# BMW_E34_Start-Stop_Btn_v2.net
KiCad netlist of a schematic drawn in Altium Designer
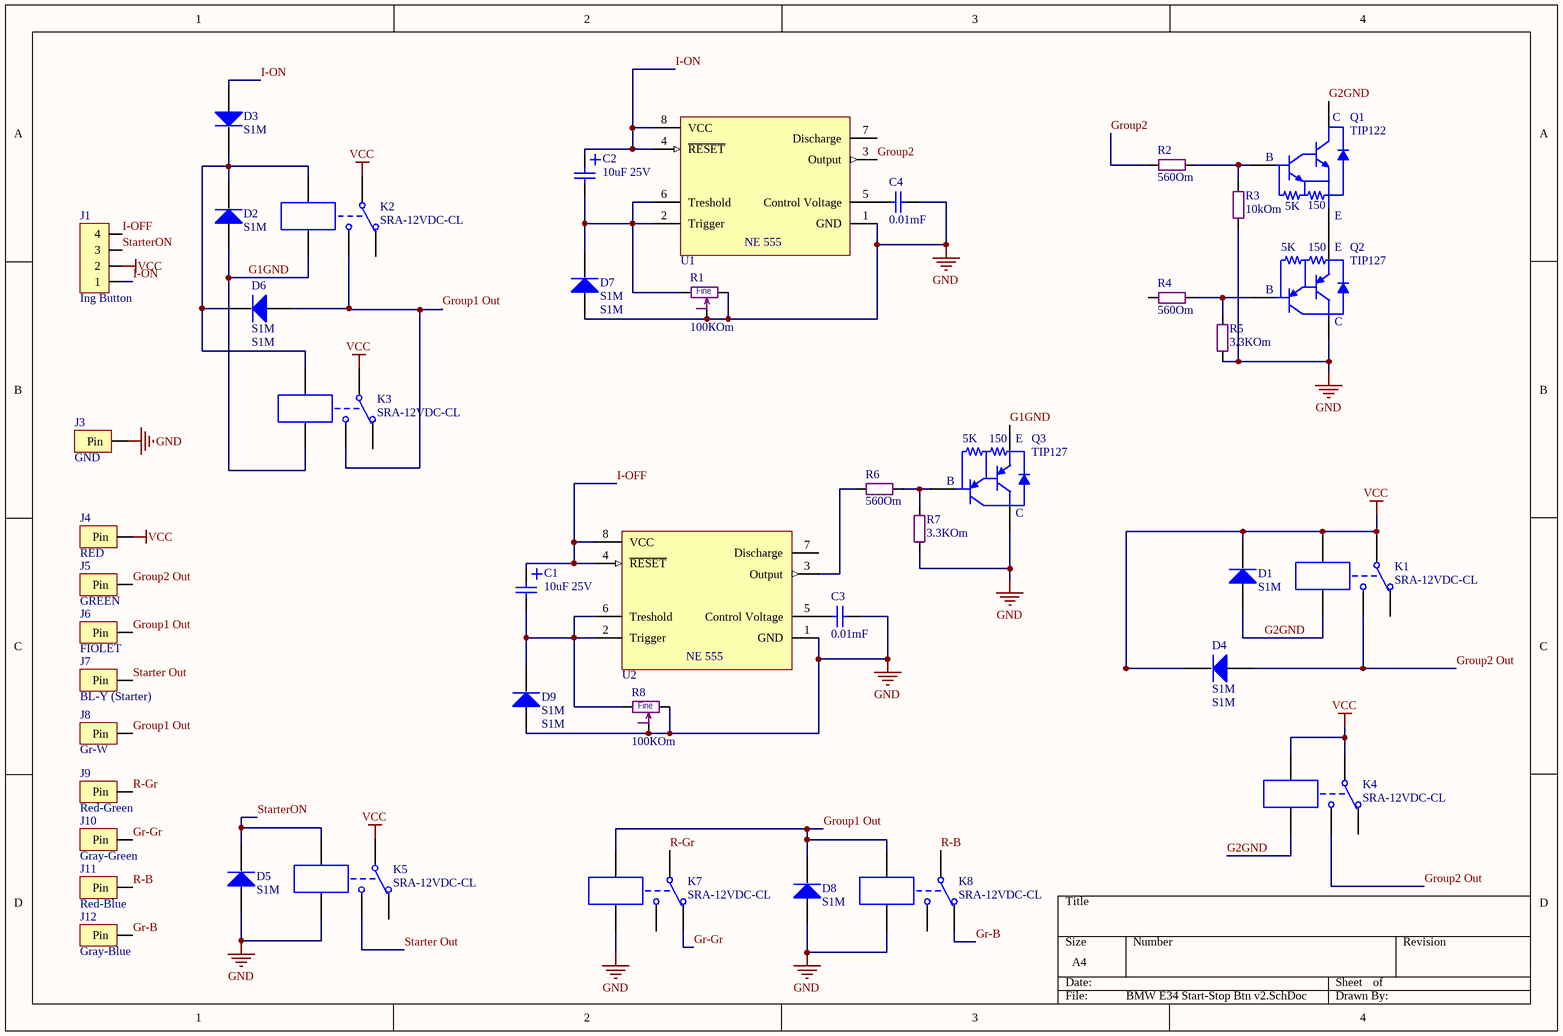
[diagram p0: BMW E34 Start-Stop Btn v2.SchDoc]

(export (version "E")
  (design (tool "Eeschema 10.0.6"))
  (components
    (comp (ref "C1")
      (value "10uF 25V")
      (footprint "Capacitor:Cap E p2mm D6.5xH11")
      (description "Capacitor")
      (libsource (lib "Capacitor") (part "Cap E 220mF x 16V"))
    )
    (comp (ref "C2")
      (value "10uF 25V")
      (footprint "Capacitor:Cap E p2mm D6.5xH11")
      (description "Capacitor")
      (libsource (lib "Capacitor") (part "Cap E 220mF x 16V"))
    )
    (comp (ref "C3")
      (value "0.01mF")
      (footprint "Capacitor:Cap p2.54mm (2p)")
      (description "Capacitor")
      (libsource (lib "Capacitor") (part "Cap Ceramic"))
    )
    (comp (ref "C4")
      (value "0.01mF")
      (footprint "Capacitor:Cap p2.54mm (2p)")
      (description "Capacitor")
      (libsource (lib "Capacitor") (part "Cap Ceramic"))
    )
    (comp (ref "D1")
      (value "S1M")
      (footprint "Diodes:DO-214AC")
      (description "1 Amp General Purpose Rectifier")
      (libsource (lib "Diodes") (part "Diode S1M"))
    )
    (comp (ref "D2")
      (value "S1M")
      (footprint "Diodes:DO-214AC")
      (description "1 Amp General Purpose Rectifier")
      (libsource (lib "Diodes") (part "Diode S1M"))
    )
    (comp (ref "D3")
      (value "S1M")
      (footprint "Diodes:DO-214AC")
      (description "1 Amp General Purpose Rectifier")
      (libsource (lib "Diodes") (part "Diode S1M"))
    )
    (comp (ref "D4")
      (value "S1M")
      (footprint "Diodes:DO-214AC")
      (description "1 Amp General Purpose Rectifier")
      (fields (field (name "ALTIUM_VALUE") "S1M"))
      (libsource (lib "Diodes") (part "Diode S1M"))
    )
    (comp (ref "D5")
      (value "S1M")
      (footprint "Diodes:DO-214AC")
      (description "1 Amp General Purpose Rectifier")
      (libsource (lib "Diodes") (part "Diode S1M"))
    )
    (comp (ref "D6")
      (value "S1M")
      (footprint "Diodes:DO-214AC")
      (description "1 Amp General Purpose Rectifier")
      (fields (field (name "ALTIUM_VALUE") "S1M"))
      (libsource (lib "Diodes") (part "Diode S1M"))
    )
    (comp (ref "D7")
      (value "S1M")
      (footprint "Diodes:DO-214AC")
      (description "1 Amp General Purpose Rectifier")
      (fields (field (name "ALTIUM_VALUE") "S1M"))
      (libsource (lib "Diodes") (part "Diode S1M"))
    )
    (comp (ref "D8")
      (value "S1M")
      (footprint "Diodes:DO-214AC")
      (description "1 Amp General Purpose Rectifier")
      (libsource (lib "Diodes") (part "Diode S1M"))
    )
    (comp (ref "D9")
      (value "S1M")
      (footprint "Diodes:DO-214AC")
      (description "1 Amp General Purpose Rectifier")
      (fields (field (name "ALTIUM_VALUE") "S1M"))
      (libsource (lib "Diodes") (part "Diode S1M"))
    )
    (comp (ref "J1")
      (value "Ing Button")
      (footprint "Connector:Molex Micro-Fit 3.0 - 4 pin D R")
      (description "Horisontal, Dbl line, Male - 3mm")
      (fields (field (name "PART NUMBER") "0430450402"))
      (libsource (lib "Connector") (part "Micro-Fit 4R (2x2)"))
    )
    (comp (ref "J3")
      (value "GND")
      (footprint "Connector:OnePin 1.2x3")
      (description "Only pad")
      (libsource (lib "Connector") (part "OnePin Connector"))
    )
    (comp (ref "J4")
      (value "RED")
      (footprint "Connector:OnePin 1.5x4")
      (description "Only pad")
      (libsource (lib "Connector") (part "OnePin Connector"))
    )
    (comp (ref "J5")
      (value "GREEN")
      (footprint "Connector:OnePin 1.5x4")
      (description "Only pad")
      (libsource (lib "Connector") (part "OnePin Connector"))
    )
    (comp (ref "J6")
      (value "FIOLET")
      (footprint "Connector:OnePin 1.5x4")
      (description "Only pad")
      (libsource (lib "Connector") (part "OnePin Connector"))
    )
    (comp (ref "J7")
      (value "BL-Y (Starter)")
      (footprint "Connector:OnePin 1.5x4")
      (description "Only pad")
      (libsource (lib "Connector") (part "OnePin Connector"))
    )
    (comp (ref "J8")
      (value "Gr-W")
      (footprint "Connector:OnePin 1x2.5")
      (description "Only pad")
      (libsource (lib "Connector") (part "OnePin Connector"))
    )
    (comp (ref "J9")
      (value "Red-Green")
      (footprint "Connector:OnePin 1x2.5")
      (description "Only pad")
      (libsource (lib "Connector") (part "OnePin Connector"))
    )
    (comp (ref "J10")
      (value "Gray-Green")
      (footprint "Connector:OnePin 1x2.5")
      (description "Only pad")
      (libsource (lib "Connector") (part "OnePin Connector"))
    )
    (comp (ref "J11")
      (value "Red-Blue")
      (footprint "Connector:OnePin 1x2.5")
      (description "Only pad")
      (libsource (lib "Connector") (part "OnePin Connector"))
    )
    (comp (ref "J12")
      (value "Gray-Blue")
      (footprint "Connector:OnePin 1x2.5")
      (description "Only pad")
      (libsource (lib "Connector") (part "OnePin Connector"))
    )
    (comp (ref "K1")
      (value "SRA-12VDC-CL")
      (footprint "Relay:SRA-12VDC-CL")
      (description "Single-Pole Dual-Throw Relay")
      (libsource (lib "Relay") (part "SRA-12VDC-CL"))
    )
    (comp (ref "K2")
      (value "SRA-12VDC-CL")
      (footprint "Relay:SRA-12VDC-CL")
      (description "Single-Pole Dual-Throw Relay")
      (libsource (lib "Relay") (part "SRA-12VDC-CL"))
    )
    (comp (ref "K3")
      (value "SRA-12VDC-CL")
      (footprint "Relay:SRA-12VDC-CL")
      (description "Single-Pole Dual-Throw Relay")
      (libsource (lib "Relay") (part "SRA-12VDC-CL"))
    )
    (comp (ref "K4")
      (value "SRA-12VDC-CL")
      (footprint "Relay:SRA-12VDC-CL")
      (description "Single-Pole Dual-Throw Relay")
      (libsource (lib "Relay") (part "SRA-12VDC-CL"))
    )
    (comp (ref "K5")
      (value "SRA-12VDC-CL")
      (footprint "Relay:SRA-12VDC-CL")
      (description "Single-Pole Dual-Throw Relay")
      (libsource (lib "Relay") (part "SRA-12VDC-CL"))
    )
    (comp (ref "K7")
      (value "SRA-12VDC-CL")
      (footprint "Relay:SRA-12VDC-CL")
      (description "Single-Pole Dual-Throw Relay")
      (libsource (lib "Relay") (part "SRA-12VDC-CL"))
    )
    (comp (ref "K8")
      (value "SRA-12VDC-CL")
      (footprint "Relay:SRA-12VDC-CL")
      (description "Single-Pole Dual-Throw Relay")
      (libsource (lib "Relay") (part "SRA-12VDC-CL"))
    )
    (comp (ref "Q1")
      (value "TIP122")
      (footprint "GeneralCases:TO220-2")
      (description "NPN Darlington 5A, 65W, 100V, h>1000")
      (libsource (lib "Transistor") (part "TIP122"))
    )
    (comp (ref "Q2")
      (value "TIP127")
      (footprint "GeneralCases:TO220-2")
      (description "PNP Darlington Bipolar Transistor")
      (libsource (lib "Transistor") (part "TIP127"))
    )
    (comp (ref "Q3")
      (value "TIP127")
      (footprint "GeneralCases:TO220-2")
      (description "PNP Darlington Bipolar Transistor")
      (libsource (lib "Transistor") (part "TIP127"))
    )
    (comp (ref "R1")
      (value "100КOm")
      (footprint "PassiveComponents:Res Adj 3362P")
      (libsource (lib "PassiveComponents") (part "Res Adj 3362"))
    )
    (comp (ref "R2")
      (value "560Om")
      (footprint "PassiveComponents:SMD 0805 (2012)")
      (libsource (lib "PassiveComponents") (part "Res All Types"))
    )
    (comp (ref "R3")
      (value "10kOm")
      (footprint "PassiveComponents:SMD 0805 (2012)")
      (libsource (lib "PassiveComponents") (part "Res All Types"))
    )
    (comp (ref "R4")
      (value "560Om")
      (footprint "PassiveComponents:SMD 0805 (2012)")
      (libsource (lib "PassiveComponents") (part "Res All Types"))
    )
    (comp (ref "R5")
      (value "3.3KOm")
      (footprint "PassiveComponents:SMD 0805 (2012)")
      (libsource (lib "PassiveComponents") (part "Res All Types"))
    )
    (comp (ref "R6")
      (value "560Om")
      (footprint "PassiveComponents:SMD 0805 (2012)")
      (libsource (lib "PassiveComponents") (part "Res All Types"))
    )
    (comp (ref "R7")
      (value "3.3KOm")
      (footprint "PassiveComponents:SMD 0805 (2012)")
      (libsource (lib "PassiveComponents") (part "Res All Types"))
    )
    (comp (ref "R8")
      (value "100КOm")
      (footprint "PassiveComponents:Res Adj 3362P")
      (libsource (lib "PassiveComponents") (part "Res Adj 3362"))
    )
    (comp (ref "U1")
      (value "NE555")
      (footprint "GeneralCases:DIP-8")
      (description "8-Bit Shift Register with 3-State Output Registers")
      (libsource (lib "Chips") (part "NE555"))
    )
    (comp (ref "U2")
      (value "NE555")
      (footprint "GeneralCases:DIP-8")
      (description "8-Bit Shift Register with 3-State Output Registers")
      (libsource (lib "Chips") (part "NE555"))
    )
  )
  (nets
    (net (code "1") (name "/G1GND") (class "Default")
      (node (ref "D2") (pin "A") (pinfunction "A_A") (pintype "passive"))
      (node (ref "K2") (pin "5") (pinfunction "5_5") (pintype "passive"))
      (node (ref "K3") (pin "5") (pinfunction "5_5") (pintype "passive"))
      (node (ref "Q3") (pin "3") (pinfunction "E_3") (pintype "passive"))
    )
    (net (code "2") (name "/G2GND") (class "Default")
      (node (ref "D1") (pin "A") (pinfunction "A_A") (pintype "passive"))
      (node (ref "K1") (pin "5") (pinfunction "5_5") (pintype "passive"))
      (node (ref "K4") (pin "5") (pinfunction "5_5") (pintype "passive"))
      (node (ref "Q1") (pin "2") (pinfunction "C_2") (pintype "passive"))
    )
    (net (code "3") (name "/Gr-B") (class "Default")
      (node (ref "J12") (pin "1") (pinfunction "Pin_1") (pintype "passive"))
      (node (ref "K8") (pin "1") (pinfunction "1_1") (pintype "passive"))
    )
    (net (code "4") (name "/Gr-Gr") (class "Default")
      (node (ref "J10") (pin "1") (pinfunction "Pin_1") (pintype "passive"))
      (node (ref "K7") (pin "1") (pinfunction "1_1") (pintype "passive"))
    )
    (net (code "5") (name "/Group1 Out") (class "Default")
      (node (ref "D6") (pin "A") (pinfunction "A_A") (pintype "passive"))
      (node (ref "D8") (pin "K") (pinfunction "K_K") (pintype "passive"))
      (node (ref "J6") (pin "1") (pinfunction "Pin_1") (pintype "passive"))
      (node (ref "J8") (pin "1") (pinfunction "Pin_1") (pintype "passive"))
      (node (ref "K2") (pin "3") (pinfunction "3_3") (pintype "passive"))
      (node (ref "K3") (pin "3") (pinfunction "3_3") (pintype "passive"))
      (node (ref "K7") (pin "4") (pinfunction "4_4") (pintype "passive"))
      (node (ref "K8") (pin "4") (pinfunction "4_4") (pintype "passive"))
    )
    (net (code "6") (name "/Group2") (class "Default")
      (node (ref "R2") (pin "1") (pinfunction "1_1") (pintype "passive"))
      (node (ref "U1") (pin "3") (pinfunction "Output_3") (pintype "output"))
    )
    (net (code "7") (name "/Group2 Out") (class "Default")
      (node (ref "D4") (pin "A") (pinfunction "A_A") (pintype "passive"))
      (node (ref "J5") (pin "1") (pinfunction "Pin_1") (pintype "passive"))
      (node (ref "K1") (pin "3") (pinfunction "3_3") (pintype "passive"))
      (node (ref "K4") (pin "3") (pinfunction "3_3") (pintype "passive"))
    )
    (net (code "8") (name "/I-OFF") (class "Default")
      (node (ref "C1") (pin "1") (pinfunction "1_1") (pintype "passive"))
      (node (ref "J1") (pin "4") (pinfunction "4_4") (pintype "passive"))
      (node (ref "U2") (pin "4") (pinfunction "~{RESET}_4") (pintype "input"))
      (node (ref "U2") (pin "8") (pinfunction "VCC_8") (pintype "power_in"))
    )
    (net (code "9") (name "/I-ON") (class "Default")
      (node (ref "C2") (pin "1") (pinfunction "1_1") (pintype "passive"))
      (node (ref "D3") (pin "A") (pinfunction "A_A") (pintype "passive"))
      (node (ref "J1") (pin "1") (pinfunction "1_1") (pintype "passive"))
      (node (ref "U1") (pin "4") (pinfunction "~{RESET}_4") (pintype "input"))
      (node (ref "U1") (pin "8") (pinfunction "VCC_8") (pintype "power_in"))
    )
    (net (code "10") (name "/R-B") (class "Default")
      (node (ref "J11") (pin "1") (pinfunction "Pin_1") (pintype "passive"))
      (node (ref "K8") (pin "2") (pinfunction "2_2") (pintype "passive"))
    )
    (net (code "11") (name "/R-Gr") (class "Default")
      (node (ref "J9") (pin "1") (pinfunction "Pin_1") (pintype "passive"))
      (node (ref "K7") (pin "2") (pinfunction "2_2") (pintype "passive"))
    )
    (net (code "12") (name "/Starter Out") (class "Default")
      (node (ref "J7") (pin "1") (pinfunction "Pin_1") (pintype "passive"))
      (node (ref "K5") (pin "3") (pinfunction "3_3") (pintype "passive"))
    )
    (net (code "13") (name "/StarterON") (class "Default")
      (node (ref "D5") (pin "K") (pinfunction "K_K") (pintype "passive"))
      (node (ref "J1") (pin "3") (pinfunction "3_3") (pintype "passive"))
      (node (ref "K5") (pin "4") (pinfunction "4_4") (pintype "passive"))
    )
    (net (code "14") (name "GND") (class "Default")
      (node (ref "C3") (pin "2") (pinfunction "2_2") (pintype "passive"))
      (node (ref "C4") (pin "2") (pinfunction "2_2") (pintype "passive"))
      (node (ref "D5") (pin "A") (pinfunction "A_A") (pintype "passive"))
      (node (ref "D7") (pin "A") (pinfunction "A_A") (pintype "passive"))
      (node (ref "D8") (pin "A") (pinfunction "A_A") (pintype "passive"))
      (node (ref "D9") (pin "A") (pinfunction "A_A") (pintype "passive"))
      (node (ref "J3") (pin "1") (pinfunction "Pin_1") (pintype "passive"))
      (node (ref "K5") (pin "5") (pinfunction "5_5") (pintype "passive"))
      (node (ref "K7") (pin "5") (pinfunction "5_5") (pintype "passive"))
      (node (ref "K8") (pin "5") (pinfunction "5_5") (pintype "passive"))
      (node (ref "Q2") (pin "2") (pinfunction "C_2") (pintype "passive"))
      (node (ref "Q3") (pin "2") (pinfunction "C_2") (pintype "passive"))
      (node (ref "R1") (pin "2") (pinfunction "2_2") (pintype "passive"))
      (node (ref "R1") (pin "3") (pinfunction "3_3") (pintype "passive"))
      (node (ref "R3") (pin "1") (pinfunction "1_1") (pintype "passive"))
      (node (ref "R5") (pin "1") (pinfunction "1_1") (pintype "passive"))
      (node (ref "R7") (pin "1") (pinfunction "1_1") (pintype "passive"))
      (node (ref "R8") (pin "2") (pinfunction "2_2") (pintype "passive"))
      (node (ref "R8") (pin "3") (pinfunction "3_3") (pintype "passive"))
      (node (ref "U1") (pin "1") (pinfunction "GND_1") (pintype "power_in"))
      (node (ref "U2") (pin "1") (pinfunction "GND_1") (pintype "power_in"))
    )
    (net (code "15") (name "Net-(D2-PadK)") (class "Default")
      (node (ref "D2") (pin "K") (pinfunction "K_K") (pintype "passive"))
      (node (ref "D3") (pin "K") (pinfunction "K_K") (pintype "passive"))
      (node (ref "D6") (pin "K") (pinfunction "K_K") (pintype "passive"))
      (node (ref "K2") (pin "4") (pinfunction "4_4") (pintype "passive"))
      (node (ref "K3") (pin "4") (pinfunction "4_4") (pintype "passive"))
    )
    (net (code "16") (name "Net-(Q1-B)") (class "Default")
      (node (ref "Q1") (pin "1") (pinfunction "B_1") (pintype "passive"))
      (node (ref "R2") (pin "2") (pinfunction "2_2") (pintype "passive"))
      (node (ref "R3") (pin "2") (pinfunction "2_2") (pintype "passive"))
    )
    (net (code "17") (name "Net-(Q1-E)") (class "Default")
      (node (ref "Q1") (pin "3") (pinfunction "E_3") (pintype "passive"))
      (node (ref "Q2") (pin "3") (pinfunction "E_3") (pintype "passive"))
    )
    (net (code "18") (name "Net-(Q2-B)") (class "Default")
      (node (ref "Q2") (pin "1") (pinfunction "B_1") (pintype "passive"))
      (node (ref "R4") (pin "2") (pinfunction "2_2") (pintype "passive"))
      (node (ref "R5") (pin "2") (pinfunction "2_2") (pintype "passive"))
    )
    (net (code "19") (name "Net-(Q3-B)") (class "Default")
      (node (ref "Q3") (pin "1") (pinfunction "B_1") (pintype "passive"))
      (node (ref "R6") (pin "2") (pinfunction "2_2") (pintype "passive"))
      (node (ref "R7") (pin "2") (pinfunction "2_2") (pintype "passive"))
    )
    (net (code "20") (name "Net-(U1-Control_Voltage)") (class "Default")
      (node (ref "C4") (pin "1") (pinfunction "1_1") (pintype "passive"))
      (node (ref "U1") (pin "5") (pinfunction "Control_Voltage_5") (pintype "tri_state"))
    )
    (net (code "21") (name "Net-(U1-Treshold)") (class "Default")
      (node (ref "C2") (pin "2") (pinfunction "2_2") (pintype "passive"))
      (node (ref "D7") (pin "K") (pinfunction "K_K") (pintype "passive"))
      (node (ref "R1") (pin "1") (pinfunction "1_1") (pintype "passive"))
      (node (ref "U1") (pin "2") (pinfunction "Trigger_2") (pintype "tri_state"))
      (node (ref "U1") (pin "6") (pinfunction "Treshold_6") (pintype "tri_state"))
    )
    (net (code "22") (name "Net-(U2-Control_Voltage)") (class "Default")
      (node (ref "C3") (pin "1") (pinfunction "1_1") (pintype "passive"))
      (node (ref "U2") (pin "5") (pinfunction "Control_Voltage_5") (pintype "tri_state"))
    )
    (net (code "23") (name "Net-(U2-Output)") (class "Default")
      (node (ref "R6") (pin "1") (pinfunction "1_1") (pintype "passive"))
      (node (ref "U2") (pin "3") (pinfunction "Output_3") (pintype "output"))
    )
    (net (code "24") (name "Net-(U2-Treshold)") (class "Default")
      (node (ref "C1") (pin "2") (pinfunction "2_2") (pintype "passive"))
      (node (ref "D9") (pin "K") (pinfunction "K_K") (pintype "passive"))
      (node (ref "R8") (pin "1") (pinfunction "1_1") (pintype "passive"))
      (node (ref "U2") (pin "2") (pinfunction "Trigger_2") (pintype "tri_state"))
      (node (ref "U2") (pin "6") (pinfunction "Treshold_6") (pintype "tri_state"))
    )
    (net (code "25") (name "VCC") (class "Default")
      (node (ref "D1") (pin "K") (pinfunction "K_K") (pintype "passive"))
      (node (ref "D4") (pin "K") (pinfunction "K_K") (pintype "passive"))
      (node (ref "J1") (pin "2") (pinfunction "2_2") (pintype "passive"))
      (node (ref "J4") (pin "1") (pinfunction "Pin_1") (pintype "passive"))
      (node (ref "K1") (pin "2") (pinfunction "2_2") (pintype "passive"))
      (node (ref "K1") (pin "4") (pinfunction "4_4") (pintype "passive"))
      (node (ref "K2") (pin "2") (pinfunction "2_2") (pintype "passive"))
      (node (ref "K3") (pin "2") (pinfunction "2_2") (pintype "passive"))
      (node (ref "K4") (pin "2") (pinfunction "2_2") (pintype "passive"))
      (node (ref "K4") (pin "4") (pinfunction "4_4") (pintype "passive"))
      (node (ref "K5") (pin "2") (pinfunction "2_2") (pintype "passive"))
    )
    (net (code "26") (name "unconnected-(K1-Pad1)") (class "Default")
      (node (ref "K1") (pin "1") (pinfunction "1_1") (pintype "passive"))
    )
    (net (code "27") (name "unconnected-(K2-Pad1)") (class "Default")
      (node (ref "K2") (pin "1") (pinfunction "1_1") (pintype "passive"))
    )
    (net (code "28") (name "unconnected-(K3-Pad1)") (class "Default")
      (node (ref "K3") (pin "1") (pinfunction "1_1") (pintype "passive"))
    )
    (net (code "29") (name "unconnected-(K4-Pad1)") (class "Default")
      (node (ref "K4") (pin "1") (pinfunction "1_1") (pintype "passive"))
    )
    (net (code "30") (name "unconnected-(K5-Pad1)") (class "Default")
      (node (ref "K5") (pin "1") (pinfunction "1_1") (pintype "passive"))
    )
    (net (code "31") (name "unconnected-(K7-Pad3)") (class "Default")
      (node (ref "K7") (pin "3") (pinfunction "3_3") (pintype "passive"))
    )
    (net (code "32") (name "unconnected-(K8-Pad3)") (class "Default")
      (node (ref "K8") (pin "3") (pinfunction "3_3") (pintype "passive"))
    )
    (net (code "33") (name "unconnected-(R4-Pad1)") (class "Default")
      (node (ref "R4") (pin "1") (pinfunction "1_1") (pintype "passive"))
    )
    (net (code "34") (name "unconnected-(U1-Discharge-Pad7)") (class "Default")
      (node (ref "U1") (pin "7") (pinfunction "Discharge_7") (pintype "tri_state"))
    )
    (net (code "35") (name "unconnected-(U2-Discharge-Pad7)") (class "Default")
      (node (ref "U2") (pin "7") (pinfunction "Discharge_7") (pintype "tri_state"))
    )
  )
)
